# MEAS_CPU.net
KiCad netlist of a schematic drawn in Altium Designer
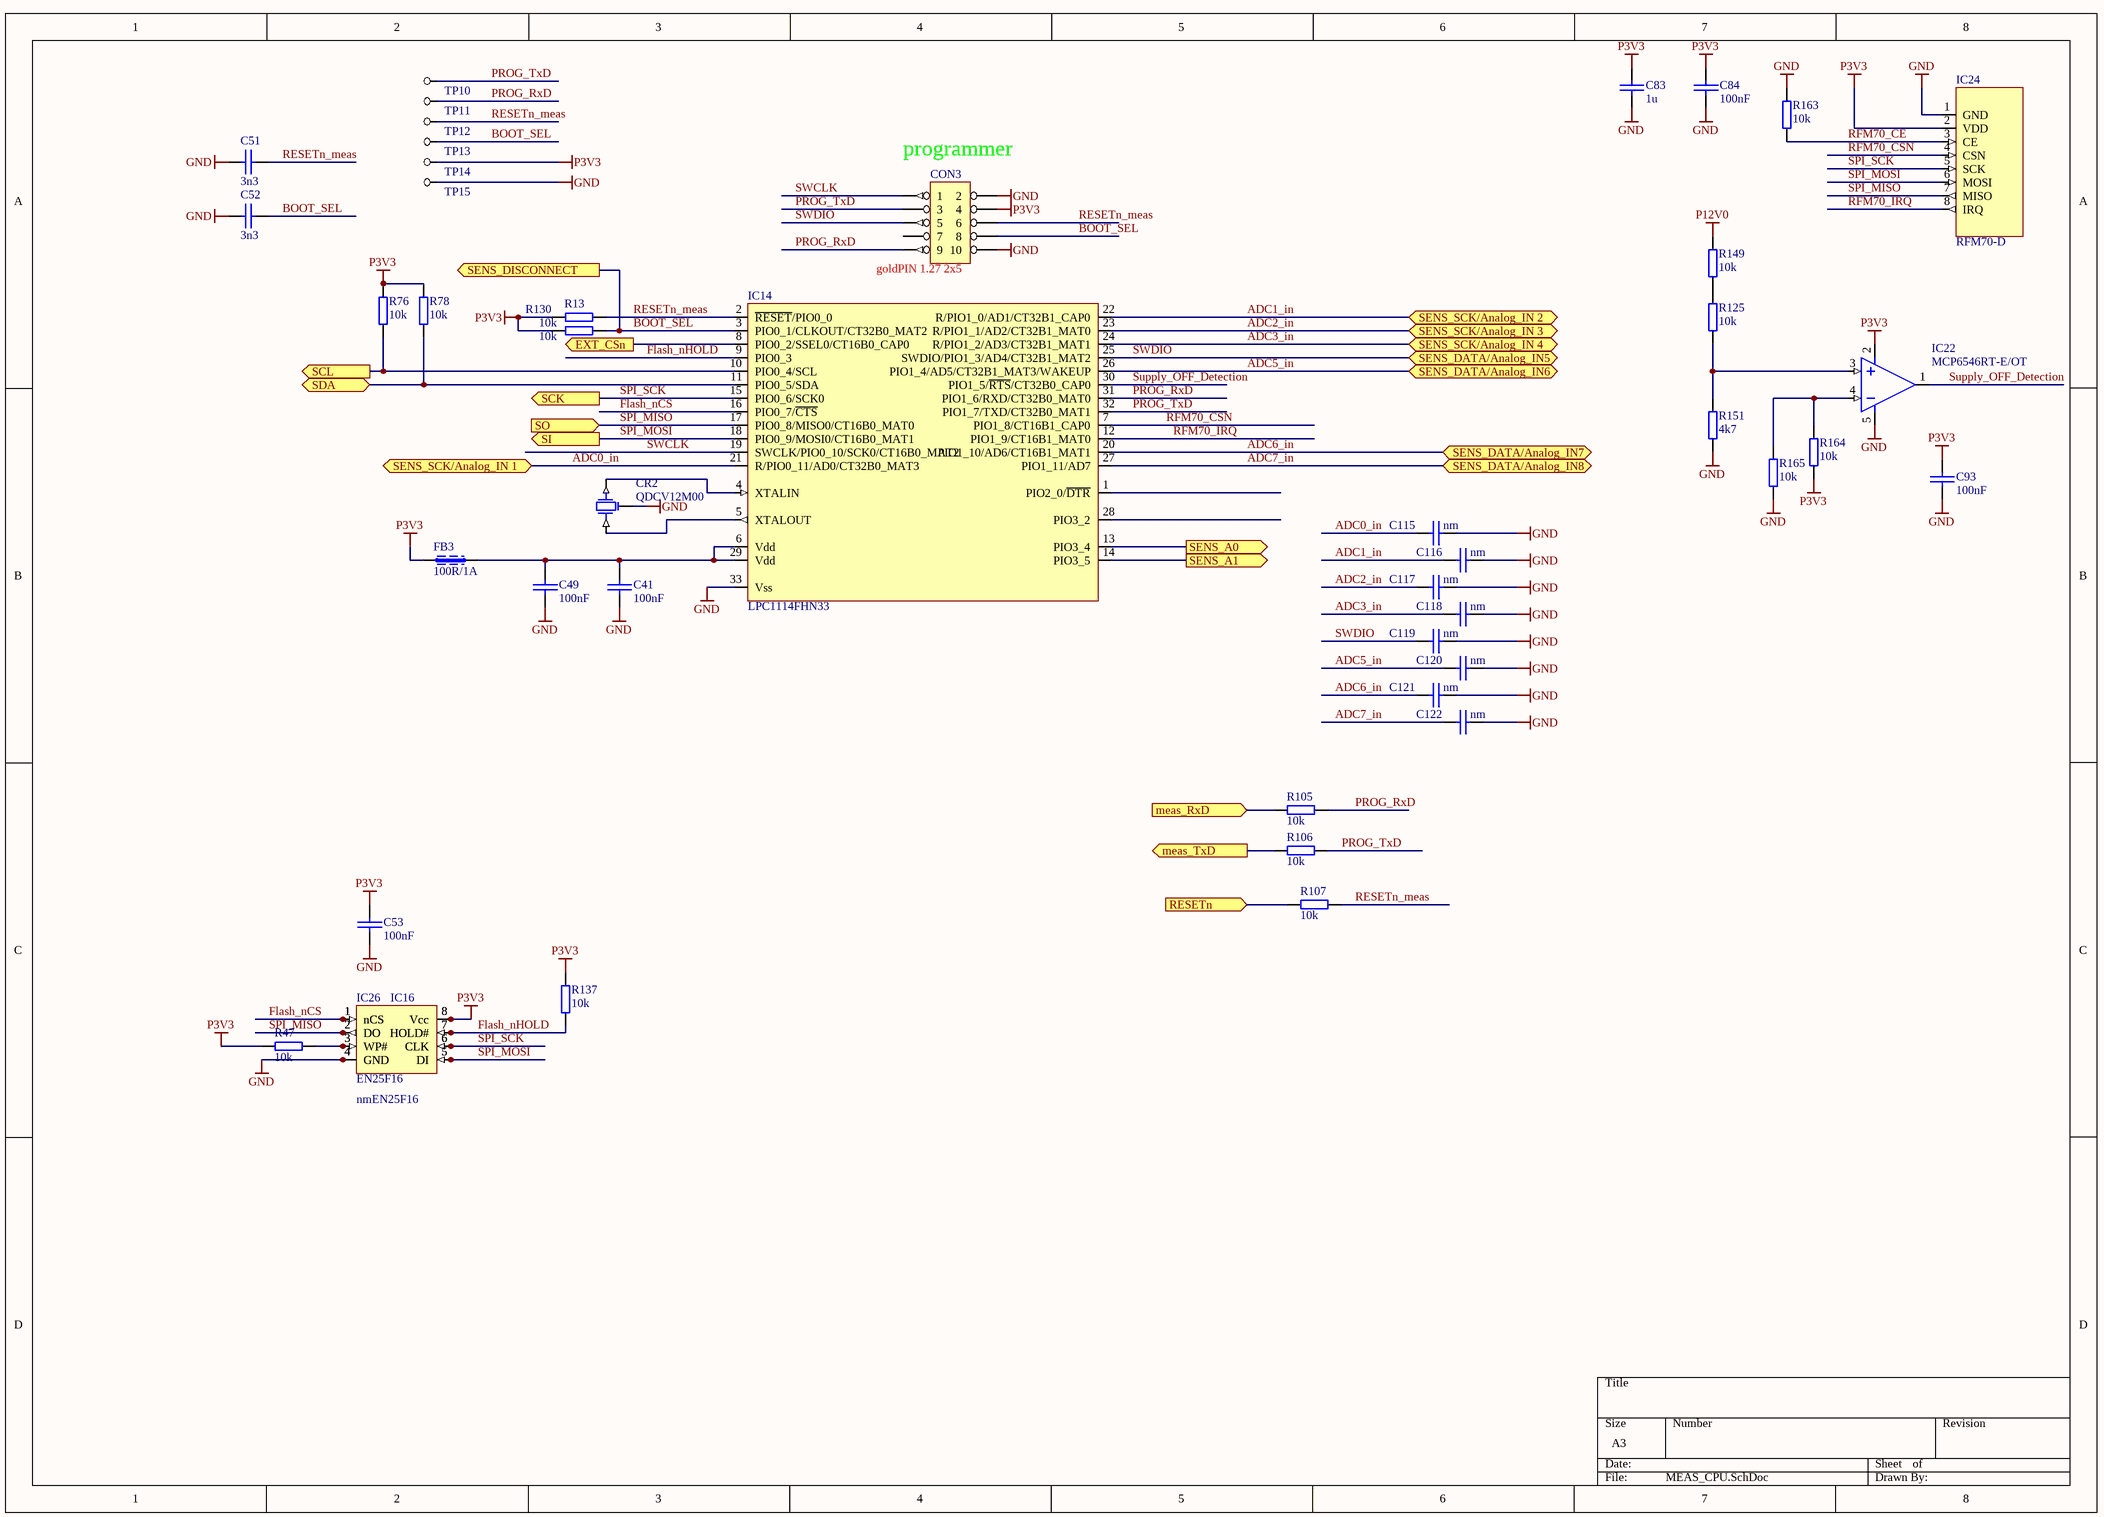
[diagram p0: MEAS_CPU.SchDoc]

(export (version "E")
  (design (tool "Eeschema 10.0.6"))
  (components
    (comp (ref "C41")
      (value "100nF")
      (footprint "0402C")
      (description "Capacitor SMD")
      (libsource (lib "LIBRARY_SCH") (part "CAP_SMD_0402"))
    )
    (comp (ref "C49")
      (value "100nF")
      (footprint "0402C")
      (description "Capacitor SMD")
      (libsource (lib "LIBRARY_SCH") (part "CAP_SMD_0402"))
    )
    (comp (ref "C51")
      (value "3n3")
      (footprint "0603C")
      (description "Capacitor SMD")
      (libsource (lib "LIBRARY_SCH") (part "CAP_SMD_0603"))
    )
    (comp (ref "C52")
      (value "3n3")
      (footprint "0603C")
      (description "Capacitor SMD")
      (libsource (lib "LIBRARY_SCH") (part "CAP_SMD_0603"))
    )
    (comp (ref "C53")
      (value "100nF")
      (footprint "0402C")
      (description "Capacitor SMD")
      (libsource (lib "LIBRARY_SCH") (part "CAP_SMD_0402"))
    )
    (comp (ref "C83")
      (value "1u")
      (footprint "0603C")
      (description "Capacitor SMD")
      (libsource (lib "LIBRARY_SCH") (part "CAP_SMD_0603"))
    )
    (comp (ref "C84")
      (value "100nF")
      (footprint "0402C")
      (description "Capacitor SMD")
      (libsource (lib "LIBRARY_SCH") (part "CAP_SMD_0402"))
    )
    (comp (ref "C93")
      (value "100nF")
      (footprint "0402C")
      (description "Capacitor SMD")
      (libsource (lib "LIBRARY_SCH") (part "CAP_SMD_0402"))
    )
    (comp (ref "C115")
      (value "nm")
      (footprint "0402C")
      (description "Capacitor SMD")
      (libsource (lib "LIBRARY_SCH") (part "CAP_SMD_0402"))
    )
    (comp (ref "C116")
      (value "nm")
      (footprint "0402C")
      (description "Capacitor SMD")
      (libsource (lib "LIBRARY_SCH") (part "CAP_SMD_0402"))
    )
    (comp (ref "C117")
      (value "nm")
      (footprint "0402C")
      (description "Capacitor SMD")
      (libsource (lib "LIBRARY_SCH") (part "CAP_SMD_0402"))
    )
    (comp (ref "C118")
      (value "nm")
      (footprint "0402C")
      (description "Capacitor SMD")
      (libsource (lib "LIBRARY_SCH") (part "CAP_SMD_0402"))
    )
    (comp (ref "C119")
      (value "nm")
      (footprint "0402C")
      (description "Capacitor SMD")
      (libsource (lib "LIBRARY_SCH") (part "CAP_SMD_0402"))
    )
    (comp (ref "C120")
      (value "nm")
      (footprint "0402C")
      (description "Capacitor SMD")
      (libsource (lib "LIBRARY_SCH") (part "CAP_SMD_0402"))
    )
    (comp (ref "C121")
      (value "nm")
      (footprint "0402C")
      (description "Capacitor SMD")
      (libsource (lib "LIBRARY_SCH") (part "CAP_SMD_0402"))
    )
    (comp (ref "C122")
      (value "nm")
      (footprint "0402C")
      (description "Capacitor SMD")
      (libsource (lib "LIBRARY_SCH") (part "CAP_SMD_0402"))
    )
    (comp (ref "CON3")
      (value "goldPIN 1.27 2x5")
      (footprint "CON_2x5_MINI")
      (libsource (lib "*") (part "HEADER 5X2"))
    )
    (comp (ref "CR2")
      (value "QDCV12M00")
      (footprint "CERAMIC_RES_QDCV")
      (description "ceramic resonator QCC(QDCV)12.00 (Maritex)")
      (libsource (lib "LIBRARY_SCH") (part "X_CERAMIC_RES"))
    )
    (comp (ref "FB3")
      (value "100R/1A")
      (footprint "0603L")
      (description "ferrite bead")
      (libsource (lib "*") (part "L_FERRITE_BEAD"))
    )
    (comp (ref "IC14")
      (value "LPC1114FHN33")
      (footprint "HVQFN33_QFN127P600-8N")
      (libsource (lib "LIBRARY_SCH") (part "UPC_LPC1111"))
    )
    (comp (ref "IC16")
      (value "EN25F16")
      (footprint "SO-8")
      (description "FLASH (maritex)")
      (libsource (lib "LIBRARY_SCH") (part "MEM_EN25F16"))
    )
    (comp (ref "IC22")
      (value "MCP6546RT-E/OT")
      (footprint "SOT23-5")
      (description "Open-Drain Output Sub-Microamp Comparators")
      (libsource (lib "ProjectLib") (part "CMP_MCP6546RT-E/OT"))
    )
    (comp (ref "IC24")
      (value "RFM70-D")
      (footprint "RFM70-D")
      (description "Low Power High Performance 2.4 GHz GFSK Transceiver Module")
      (libsource (lib "ProjectLib") (part "RFM70-D"))
    )
    (comp (ref "IC26")
      (value "nmEN25F16")
      (footprint "SO-8L")
      (description "FLASH (maritex)")
      (libsource (lib "LIBRARY_SCH") (part "MEM_EN25F16"))
    )
    (comp (ref "R13")
      (value "10k")
      (footprint "0402R")
      (description "SMD Resistor")
      (libsource (lib "LIBRARY_SCH") (part "RES_0402"))
    )
    (comp (ref "R47")
      (value "10k")
      (footprint "0402R")
      (description "SMD Resistor")
      (libsource (lib "LIBRARY_SCH") (part "RES_0402"))
    )
    (comp (ref "R76")
      (value "10k")
      (footprint "0402R")
      (description "SMD Resistor")
      (libsource (lib "LIBRARY_SCH") (part "RES_0402"))
    )
    (comp (ref "R78")
      (value "10k")
      (footprint "0402R")
      (description "SMD Resistor")
      (libsource (lib "LIBRARY_SCH") (part "RES_0402"))
    )
    (comp (ref "R105")
      (value "10k")
      (footprint "0402R")
      (description "SMD Resistor")
      (libsource (lib "LIBRARY_SCH") (part "RES_0402"))
    )
    (comp (ref "R106")
      (value "10k")
      (footprint "0402R")
      (description "SMD Resistor")
      (libsource (lib "LIBRARY_SCH") (part "RES_0402"))
    )
    (comp (ref "R107")
      (value "10k")
      (footprint "0402R")
      (description "SMD Resistor")
      (libsource (lib "LIBRARY_SCH") (part "RES_0402"))
    )
    (comp (ref "R125")
      (value "10k")
      (footprint "0402R")
      (description "SMD Resistor")
      (libsource (lib "LIBRARY_SCH") (part "RES_0402"))
    )
    (comp (ref "R130")
      (value "10k")
      (footprint "0402R")
      (description "SMD Resistor")
      (libsource (lib "LIBRARY_SCH") (part "RES_0402"))
    )
    (comp (ref "R137")
      (value "10k")
      (footprint "0402R")
      (description "SMD Resistor")
      (libsource (lib "LIBRARY_SCH") (part "RES_0402"))
    )
    (comp (ref "R149")
      (value "10k")
      (footprint "0402R")
      (description "SMD Resistor")
      (libsource (lib "LIBRARY_SCH") (part "RES_0402"))
    )
    (comp (ref "R151")
      (value "4k7")
      (footprint "0402R")
      (description "SMD Resistor")
      (libsource (lib "LIBRARY_SCH") (part "RES_0402"))
    )
    (comp (ref "R163")
      (value "10k")
      (footprint "0402R")
      (description "SMD Resistor")
      (libsource (lib "LIBRARY_SCH") (part "RES_0402"))
    )
    (comp (ref "R164")
      (value "10k")
      (footprint "0402R")
      (description "SMD Resistor")
      (libsource (lib "LIBRARY_SCH") (part "RES_0402"))
    )
    (comp (ref "R165")
      (value "10k")
      (footprint "0402R")
      (description "SMD Resistor")
      (libsource (lib "LIBRARY_SCH") (part "RES_0402"))
    )
    (comp (ref "TP10")
      (value "TP_PROG_TxD")
      (footprint "TP_large")
      (description "Testpoint")
      (libsource (lib "LIBRARY_SCH") (part "TP"))
    )
    (comp (ref "TP11")
      (value "TP_PROG_RxD")
      (footprint "TP_large")
      (description "Testpoint")
      (libsource (lib "LIBRARY_SCH") (part "TP"))
    )
    (comp (ref "TP12")
      (value "TP_RESETn")
      (footprint "TP_large")
      (description "Testpoint")
      (libsource (lib "LIBRARY_SCH") (part "TP"))
    )
    (comp (ref "TP13")
      (value "TP_BOOT_SEL")
      (footprint "TP_large")
      (description "Testpoint")
      (libsource (lib "LIBRARY_SCH") (part "TP"))
    )
    (comp (ref "TP14")
      (value "TP_3V3_meas")
      (footprint "TP_large")
      (description "Testpoint")
      (libsource (lib "LIBRARY_SCH") (part "TP"))
    )
    (comp (ref "TP15")
      (value "TP_GND_meas")
      (footprint "TP_large")
      (description "Testpoint")
      (libsource (lib "LIBRARY_SCH") (part "TP"))
    )
  )
  (nets
    (net (code "1") (name "/ADC0_in") (class "Default")
      (node (ref "C115") (pin "2") (pinfunction "2_2") (pintype "passive"))
      (node (ref "IC14") (pin "21") (pinfunction "R/PIO0_11/AD0/CT32B0_MAT3_21") (pintype "bidirectional"))
    )
    (net (code "2") (name "/ADC1_in") (class "Default")
      (node (ref "C116") (pin "2") (pinfunction "2_2") (pintype "passive"))
      (node (ref "IC14") (pin "22") (pinfunction "R/PIO1_0/AD1/CT32B1_CAP0_22") (pintype "bidirectional"))
    )
    (net (code "3") (name "/ADC2_in") (class "Default")
      (node (ref "C117") (pin "2") (pinfunction "2_2") (pintype "passive"))
      (node (ref "IC14") (pin "23") (pinfunction "R/PIO1_1/AD2/CT32B1_MAT0_23") (pintype "bidirectional"))
    )
    (net (code "4") (name "/ADC3_in") (class "Default")
      (node (ref "C118") (pin "2") (pinfunction "2_2") (pintype "passive"))
      (node (ref "IC14") (pin "24") (pinfunction "R/PIO1_2/AD3/CT32B1_MAT1_24") (pintype "bidirectional"))
    )
    (net (code "5") (name "/ADC5_in") (class "Default")
      (node (ref "C120") (pin "2") (pinfunction "2_2") (pintype "passive"))
      (node (ref "IC14") (pin "26") (pinfunction "PIO1_4/AD5/CT32B1_MAT3/WAKEUP_26") (pintype "bidirectional"))
    )
    (net (code "6") (name "/ADC6_in") (class "Default")
      (node (ref "C121") (pin "2") (pinfunction "2_2") (pintype "passive"))
      (node (ref "IC14") (pin "20") (pinfunction "PIO1_10/AD6/CT16B1_MAT1_20") (pintype "bidirectional"))
    )
    (net (code "7") (name "/ADC7_in") (class "Default")
      (node (ref "C122") (pin "2") (pinfunction "2_2") (pintype "passive"))
      (node (ref "IC14") (pin "27") (pinfunction "PIO1_11/AD7_27") (pintype "bidirectional"))
    )
    (net (code "8") (name "/BOOT_SEL") (class "Default")
      (node (ref "C52") (pin "2") (pinfunction "2_2") (pintype "passive"))
      (node (ref "CON3") (pin "8") (pinfunction "8_8") (pintype "passive"))
      (node (ref "IC14") (pin "3") (pinfunction "PIO0_1/CLKOUT/CT32B0_MAT2_3") (pintype "bidirectional"))
      (node (ref "R130") (pin "2") (pinfunction "2_2") (pintype "passive"))
      (node (ref "TP13") (pin "1") (pintype "passive"))
    )
    (net (code "9") (name "/EXT_CSn") (class "Default")
      (node (ref "IC14") (pin "8") (pinfunction "PIO0_2/SSEL0/CT16B0_CAP0_8") (pintype "bidirectional"))
    )
    (net (code "10") (name "/Flash_nCS") (class "Default")
      (node (ref "IC14") (pin "16") (pinfunction "PIO0_7/~{CTS}_16") (pintype "bidirectional"))
      (node (ref "IC16") (pin "1") (pinfunction "nCS_1") (pintype "input"))
      (node (ref "IC26") (pin "1") (pinfunction "nCS_1") (pintype "input"))
    )
    (net (code "11") (name "/Flash_nHOLD") (class "Default")
      (node (ref "IC14") (pin "9") (pinfunction "PIO0_3_9") (pintype "bidirectional"))
      (node (ref "IC16") (pin "7") (pinfunction "HOLD#_7") (pintype "input"))
      (node (ref "IC26") (pin "7") (pinfunction "HOLD#_7") (pintype "input"))
      (node (ref "R137") (pin "2") (pinfunction "2_2") (pintype "passive"))
    )
    (net (code "12") (name "/PROG_RxD") (class "Default")
      (node (ref "CON3") (pin "9") (pinfunction "9_9") (pintype "output"))
      (node (ref "IC14") (pin "31") (pinfunction "PIO1_6/RXD/CT32B0_MAT0_31") (pintype "bidirectional"))
      (node (ref "R105") (pin "2") (pinfunction "2_2") (pintype "passive"))
      (node (ref "TP11") (pin "1") (pintype "passive"))
    )
    (net (code "13") (name "/PROG_TxD") (class "Default")
      (node (ref "CON3") (pin "3") (pinfunction "3_3") (pintype "passive"))
      (node (ref "IC14") (pin "32") (pinfunction "PIO1_7/TXD/CT32B0_MAT1_32") (pintype "bidirectional"))
      (node (ref "R106") (pin "2") (pinfunction "2_2") (pintype "passive"))
      (node (ref "TP10") (pin "1") (pintype "passive"))
    )
    (net (code "14") (name "/RESETn") (class "Default")
      (node (ref "R107") (pin "1") (pinfunction "1_1") (pintype "passive"))
    )
    (net (code "15") (name "/RESETn_meas") (class "Default")
      (node (ref "C51") (pin "2") (pinfunction "2_2") (pintype "passive"))
      (node (ref "CON3") (pin "6") (pinfunction "6_6") (pintype "passive"))
      (node (ref "IC14") (pin "2") (pinfunction "~{RESET}/PIO0_0_2") (pintype "bidirectional"))
      (node (ref "R107") (pin "2") (pinfunction "2_2") (pintype "passive"))
      (node (ref "R13") (pin "2") (pinfunction "2_2") (pintype "passive"))
      (node (ref "TP12") (pin "1") (pintype "passive"))
    )
    (net (code "16") (name "/RFM70_CE") (class "Default")
      (node (ref "IC24") (pin "3") (pinfunction "CE_3") (pintype "input"))
      (node (ref "R163") (pin "2") (pinfunction "2_2") (pintype "passive"))
    )
    (net (code "17") (name "/RFM70_CSN") (class "Default")
      (node (ref "IC14") (pin "7") (pinfunction "PIO1_8/CT16B1_CAP0_7") (pintype "bidirectional"))
      (node (ref "IC24") (pin "4") (pinfunction "CSN_4") (pintype "input"))
    )
    (net (code "18") (name "/RFM70_IRQ") (class "Default")
      (node (ref "IC14") (pin "12") (pinfunction "PIO1_9/CT16B1_MAT0_12") (pintype "bidirectional"))
      (node (ref "IC24") (pin "8") (pinfunction "IRQ_8") (pintype "output"))
    )
    (net (code "19") (name "/SCL") (class "Default")
      (node (ref "IC14") (pin "10") (pinfunction "PIO0_4/SCL_10") (pintype "bidirectional"))
      (node (ref "R76") (pin "1") (pinfunction "1_1") (pintype "passive"))
    )
    (net (code "20") (name "/SDA") (class "Default")
      (node (ref "IC14") (pin "11") (pinfunction "PIO0_5/SDA_11") (pintype "bidirectional"))
      (node (ref "R78") (pin "1") (pinfunction "1_1") (pintype "passive"))
    )
    (net (code "21") (name "/SENS_A0") (class "Default")
      (node (ref "IC14") (pin "13") (pinfunction "PIO3_4_13") (pintype "bidirectional"))
    )
    (net (code "22") (name "/SENS_A1") (class "Default")
      (node (ref "IC14") (pin "14") (pinfunction "PIO3_5_14") (pintype "bidirectional"))
    )
    (net (code "23") (name "/SPI_MISO") (class "Default")
      (node (ref "IC14") (pin "17") (pinfunction "PIO0_8/MISO0/CT16B0_MAT0_17") (pintype "bidirectional"))
      (node (ref "IC16") (pin "2") (pinfunction "DO_2") (pintype "output"))
      (node (ref "IC24") (pin "7") (pinfunction "MISO_7") (pintype "output"))
      (node (ref "IC26") (pin "2") (pinfunction "DO_2") (pintype "output"))
    )
    (net (code "24") (name "/SPI_MOSI") (class "Default")
      (node (ref "IC14") (pin "18") (pinfunction "PIO0_9/MOSI0/CT16B0_MAT1_18") (pintype "bidirectional"))
      (node (ref "IC16") (pin "5") (pinfunction "DI_5") (pintype "input"))
      (node (ref "IC24") (pin "6") (pinfunction "MOSI_6") (pintype "input"))
      (node (ref "IC26") (pin "5") (pinfunction "DI_5") (pintype "input"))
    )
    (net (code "25") (name "/SPI_SCK") (class "Default")
      (node (ref "IC14") (pin "15") (pinfunction "PIO0_6/SCK0_15") (pintype "bidirectional"))
      (node (ref "IC16") (pin "6") (pinfunction "CLK_6") (pintype "input"))
      (node (ref "IC24") (pin "5") (pinfunction "SCK_5") (pintype "input"))
      (node (ref "IC26") (pin "6") (pinfunction "CLK_6") (pintype "input"))
    )
    (net (code "26") (name "/SWCLK") (class "Default")
      (node (ref "CON3") (pin "1") (pinfunction "1_1") (pintype "output"))
      (node (ref "IC14") (pin "19") (pinfunction "SWCLK/PIO0_10/SCK0/CT16B0_MAT2_19") (pintype "bidirectional"))
    )
    (net (code "27") (name "/SWDIO") (class "Default")
      (node (ref "C119") (pin "2") (pinfunction "2_2") (pintype "passive"))
      (node (ref "CON3") (pin "5") (pinfunction "5_5") (pintype "output"))
      (node (ref "IC14") (pin "25") (pinfunction "SWDIO/PIO1_3/AD4/CT32B1_MAT2_25") (pintype "bidirectional"))
    )
    (net (code "28") (name "/Supply_OFF_Detection") (class "Default")
      (node (ref "IC14") (pin "30") (pinfunction "PIO1_5/~{RTS}/CT32B0_CAP0_30") (pintype "bidirectional"))
      (node (ref "IC22") (pin "1") (pintype "open_collector"))
    )
    (net (code "29") (name "/meas_RxD") (class "Default")
      (node (ref "R105") (pin "1") (pinfunction "1_1") (pintype "passive"))
    )
    (net (code "30") (name "/meas_TxD") (class "Default")
      (node (ref "R106") (pin "1") (pinfunction "1_1") (pintype "passive"))
    )
    (net (code "31") (name "GND") (class "Default")
      (node (ref "C115") (pin "1") (pinfunction "1_1") (pintype "passive"))
      (node (ref "C116") (pin "1") (pinfunction "1_1") (pintype "passive"))
      (node (ref "C117") (pin "1") (pinfunction "1_1") (pintype "passive"))
      (node (ref "C118") (pin "1") (pinfunction "1_1") (pintype "passive"))
      (node (ref "C119") (pin "1") (pinfunction "1_1") (pintype "passive"))
      (node (ref "C120") (pin "1") (pinfunction "1_1") (pintype "passive"))
      (node (ref "C121") (pin "1") (pinfunction "1_1") (pintype "passive"))
      (node (ref "C122") (pin "1") (pinfunction "1_1") (pintype "passive"))
      (node (ref "C41") (pin "2") (pinfunction "2_2") (pintype "passive"))
      (node (ref "C49") (pin "2") (pinfunction "2_2") (pintype "passive"))
      (node (ref "C51") (pin "1") (pinfunction "1_1") (pintype "passive"))
      (node (ref "C52") (pin "1") (pinfunction "1_1") (pintype "passive"))
      (node (ref "C53") (pin "2") (pinfunction "2_2") (pintype "passive"))
      (node (ref "C83") (pin "2") (pinfunction "2_2") (pintype "passive"))
      (node (ref "C84") (pin "1") (pinfunction "1_1") (pintype "passive"))
      (node (ref "C93") (pin "1") (pinfunction "1_1") (pintype "passive"))
      (node (ref "CON3") (pin "10") (pinfunction "10_10") (pintype "passive"))
      (node (ref "CON3") (pin "2") (pinfunction "2_2") (pintype "passive"))
      (node (ref "CR2") (pin "2") (pinfunction "2_2") (pintype "passive"))
      (node (ref "IC14") (pin "33") (pinfunction "Vss_33") (pintype "power_in"))
      (node (ref "IC16") (pin "4") (pinfunction "GND_4") (pintype "passive"))
      (node (ref "IC22") (pin "5") (pintype "power_in"))
      (node (ref "IC24") (pin "1") (pinfunction "GND_1") (pintype "power_in"))
      (node (ref "IC26") (pin "4") (pinfunction "GND_4") (pintype "passive"))
      (node (ref "R151") (pin "1") (pinfunction "1_1") (pintype "passive"))
      (node (ref "R163") (pin "1") (pinfunction "1_1") (pintype "passive"))
      (node (ref "R165") (pin "1") (pinfunction "1_1") (pintype "passive"))
      (node (ref "TP15") (pin "1") (pintype "passive"))
    )
    (net (code "32") (name "Net-(C41-Pad1)") (class "Default")
      (node (ref "C41") (pin "1") (pinfunction "1_1") (pintype "passive"))
      (node (ref "C49") (pin "1") (pinfunction "1_1") (pintype "passive"))
      (node (ref "FB3") (pin "2") (pinfunction "2_2") (pintype "passive"))
      (node (ref "IC14") (pin "29") (pinfunction "Vdd_29") (pintype "power_in"))
      (node (ref "IC14") (pin "6") (pinfunction "Vdd_6") (pintype "power_in"))
    )
    (net (code "33") (name "Net-(IC14-XTALIN)") (class "Default")
      (node (ref "CR2") (pin "1") (pinfunction "1_1") (pintype "output"))
      (node (ref "IC14") (pin "4") (pinfunction "XTALIN_4") (pintype "input"))
    )
    (net (code "34") (name "Net-(IC14-XTALOUT)") (class "Default")
      (node (ref "CR2") (pin "3") (pinfunction "3_3") (pintype "input"))
      (node (ref "IC14") (pin "5") (pinfunction "XTALOUT_5") (pintype "output"))
    )
    (net (code "35") (name "Net-(IC16-WP#)") (class "Default")
      (node (ref "IC16") (pin "3") (pinfunction "WP#_3") (pintype "input"))
      (node (ref "IC26") (pin "3") (pinfunction "WP#_3") (pintype "input"))
      (node (ref "R47") (pin "1") (pinfunction "1_1") (pintype "passive"))
    )
    (net (code "36") (name "Net-(IC22-Pad3)") (class "Default")
      (node (ref "IC22") (pin "3") (pintype "input"))
      (node (ref "R125") (pin "1") (pinfunction "1_1") (pintype "passive"))
      (node (ref "R151") (pin "2") (pinfunction "2_2") (pintype "passive"))
    )
    (net (code "37") (name "Net-(IC22-Pad4)") (class "Default")
      (node (ref "IC22") (pin "4") (pintype "input"))
      (node (ref "R164") (pin "2") (pinfunction "2_2") (pintype "passive"))
      (node (ref "R165") (pin "2") (pinfunction "2_2") (pintype "passive"))
    )
    (net (code "38") (name "Net-(R125-Pad2)") (class "Default")
      (node (ref "R125") (pin "2") (pinfunction "2_2") (pintype "passive"))
      (node (ref "R149") (pin "1") (pinfunction "1_1") (pintype "passive"))
    )
    (net (code "39") (name "P3V3") (class "Default")
      (node (ref "C53") (pin "1") (pinfunction "1_1") (pintype "passive"))
      (node (ref "C83") (pin "1") (pinfunction "1_1") (pintype "passive"))
      (node (ref "C84") (pin "2") (pinfunction "2_2") (pintype "passive"))
      (node (ref "C93") (pin "2") (pinfunction "2_2") (pintype "passive"))
      (node (ref "CON3") (pin "4") (pinfunction "4_4") (pintype "passive"))
      (node (ref "FB3") (pin "1") (pinfunction "1_1") (pintype "passive"))
      (node (ref "IC16") (pin "8") (pinfunction "Vcc_8") (pintype "passive"))
      (node (ref "IC22") (pin "2") (pintype "power_in"))
      (node (ref "IC24") (pin "2") (pinfunction "VDD_2") (pintype "power_in"))
      (node (ref "IC26") (pin "8") (pinfunction "Vcc_8") (pintype "passive"))
      (node (ref "R13") (pin "1") (pinfunction "1_1") (pintype "passive"))
      (node (ref "R130") (pin "1") (pinfunction "1_1") (pintype "passive"))
      (node (ref "R137") (pin "1") (pinfunction "1_1") (pintype "passive"))
      (node (ref "R164") (pin "1") (pinfunction "1_1") (pintype "passive"))
      (node (ref "R47") (pin "2") (pinfunction "2_2") (pintype "passive"))
      (node (ref "R76") (pin "2") (pinfunction "2_2") (pintype "passive"))
      (node (ref "R78") (pin "2") (pinfunction "2_2") (pintype "passive"))
      (node (ref "TP14") (pin "1") (pintype "passive"))
    )
    (net (code "40") (name "P12V0") (class "Default")
      (node (ref "R149") (pin "2") (pinfunction "2_2") (pintype "passive"))
    )
    (net (code "41") (name "unconnected-(CON3-Pad7)") (class "Default")
      (node (ref "CON3") (pin "7") (pinfunction "7_7") (pintype "passive"))
    )
    (net (code "42") (name "unconnected-(IC14-PIO2_0{slash}~{DTR}-Pad1)") (class "Default")
      (node (ref "IC14") (pin "1") (pinfunction "PIO2_0/~{DTR}_1") (pintype "bidirectional"))
    )
    (net (code "43") (name "unconnected-(IC14-PIO3_2-Pad28)") (class "Default")
      (node (ref "IC14") (pin "28") (pinfunction "PIO3_2_28") (pintype "bidirectional"))
    )
  )
)
